# ai_LED_pendant.net
KiCad netlist of a schematic drawn in EAGLE
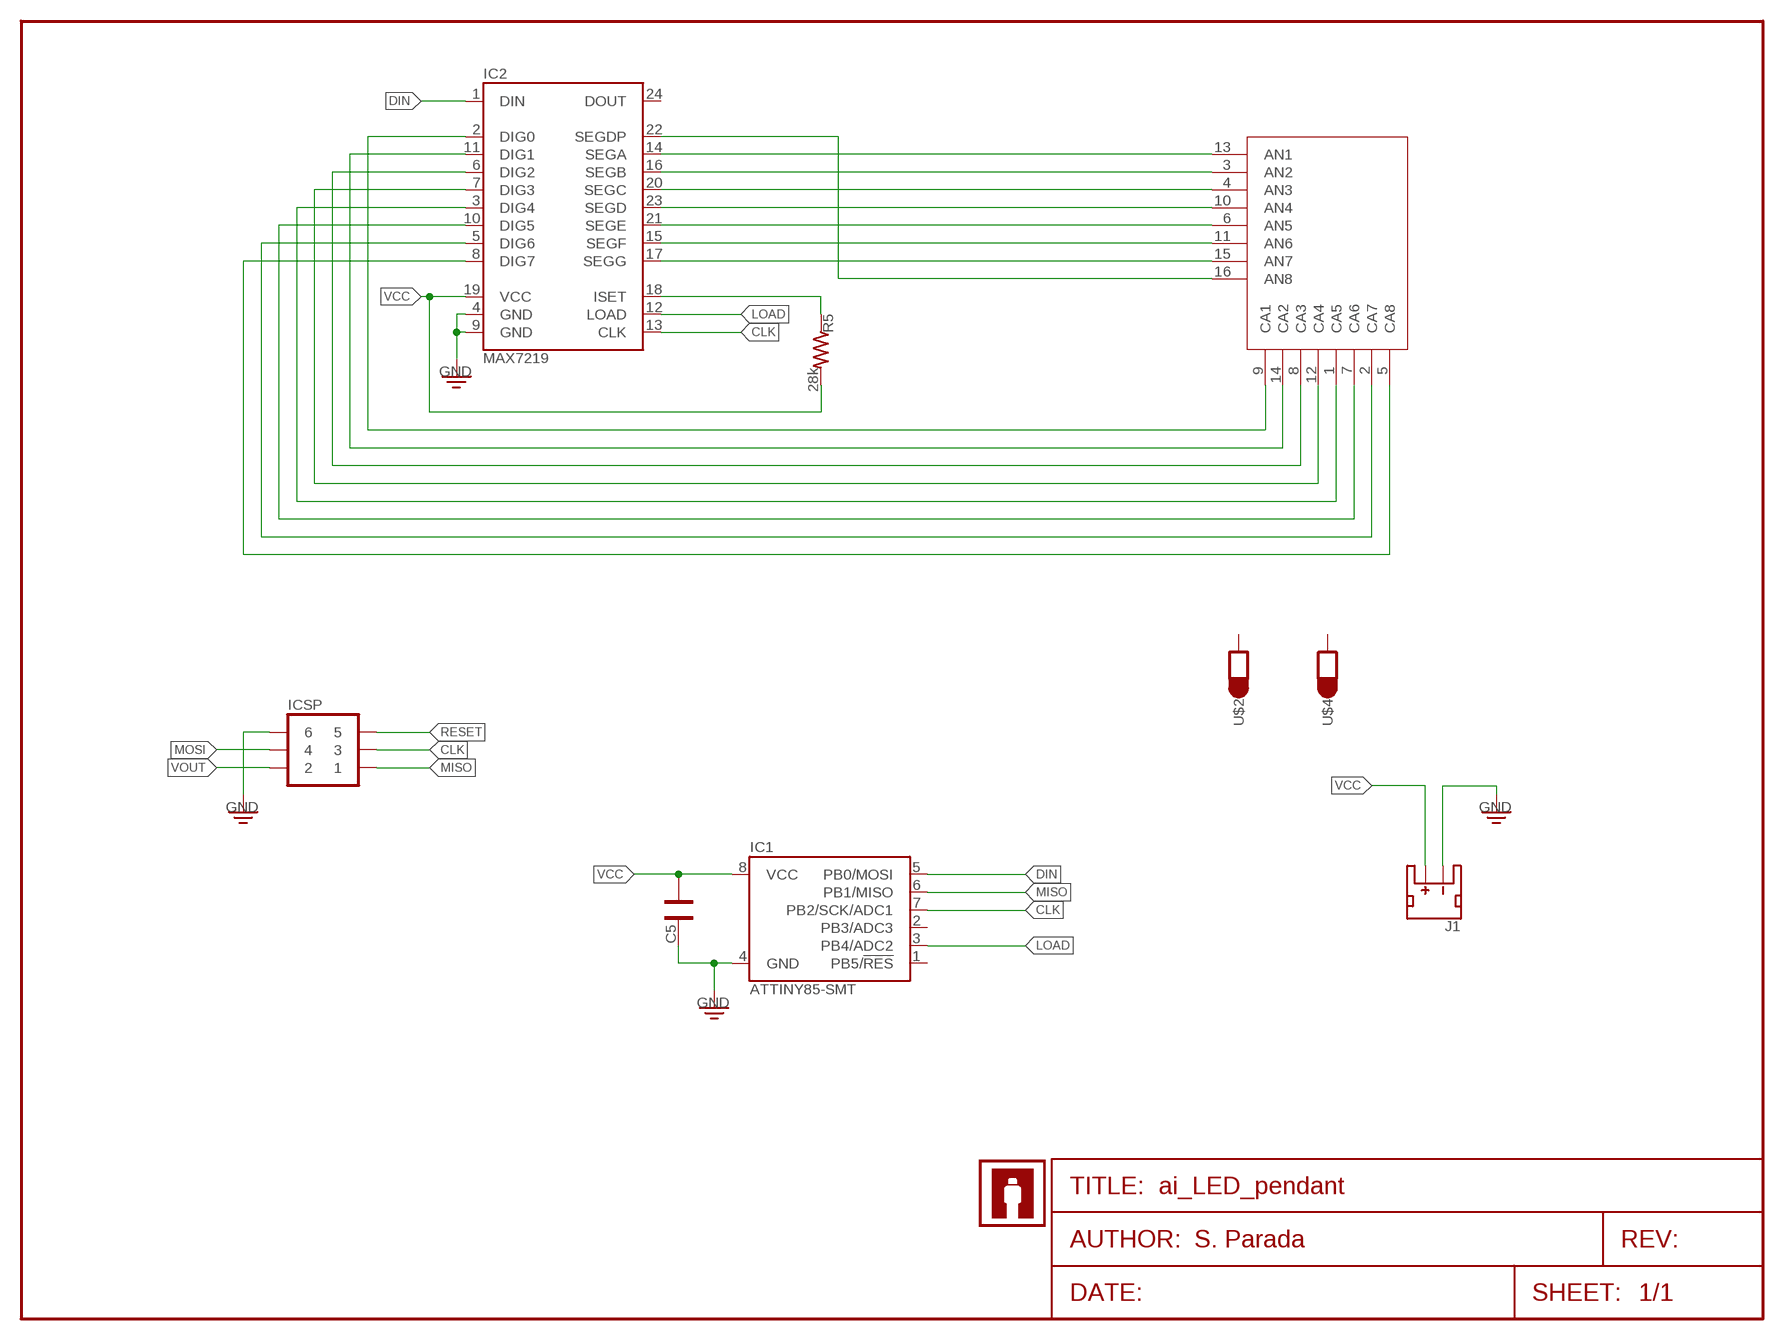
[diagram p0: schematic, sheet 1]

(export (version "E")
  (design (tool "Eeschema 10.0.6"))
  (components
    (comp (ref "C5")
      (value "CAP0402")
      (footprint "eagle-import:CAP-0402")
      (libsource (lib "eagle-import") (part "CAP0402"))
    )
    (comp (ref "IC1")
      (value "ATTINY85-SMT")
      (footprint "eagle-import:SO08-EIAJ")
      (libsource (lib "eagle-import") (part "ATTINY85-SMT"))
    )
    (comp (ref "IC2")
      (value "MAX7219-SMD")
      (footprint "eagle-import:SOIC24")
      (libsource (lib "eagle-import") (part "MAX7219-SMD"))
    )
    (comp (ref "ICSP")
      (value "2X032X03-ICSP-SMALL")
      (footprint "eagle-import:2X03-ICSP-SMALL")
      (libsource (lib "eagle-import") (part "2X032X03-ICSP-SMALL"))
    )
    (comp (ref "J1")
      (value "JST-2P-MALE")
      (footprint "eagle-import:JST-2P-SMD")
      (libsource (lib "eagle-import") (part "JST-2P-MALE"))
    )
    (comp (ref "MATRIX")
      (value "MATRIX-8X8-SINGLE")
      (footprint "eagle-import:LEDM88SMR")
      (libsource (lib "eagle-import") (part "MATRIX-8X8-SINGLE"))
    )
    (comp (ref "R5")
      (value "28k")
      (footprint "eagle-import:RES-0402")
      (libsource (lib "eagle-import") (part "RES0402"))
    )
    (comp (ref "U$1")
      (value "AI-LOGOXS")
      (footprint "eagle-import:AI-LOGO-XS")
      (libsource (lib "eagle-import") (part "AI-LOGOXS"))
    )
    (comp (ref "U$2")
      (value "1X01-PETAL")
      (footprint "eagle-import:1X01-PETAL")
      (libsource (lib "eagle-import") (part "1X01-PETAL"))
    )
    (comp (ref "U$4")
      (value "1X01-PETAL")
      (footprint "eagle-import:1X01-PETAL")
      (libsource (lib "eagle-import") (part "1X01-PETAL"))
    )
  )
  (nets
    (net (code "1") (name "CLK") (class "Default")
      (node (ref "IC1") (pin "7") (pinfunction "PB2/SCK/ADC1_7") (pintype "bidirectional"))
      (node (ref "IC2") (pin "13") (pinfunction "CLK_13") (pintype "bidirectional"))
      (node (ref "ICSP") (pin "3") (pinfunction "3_3") (pintype "bidirectional"))
    )
    (net (code "2") (name "DIN") (class "Default")
      (node (ref "IC1") (pin "5") (pinfunction "PB0/MOSI_5") (pintype "bidirectional"))
      (node (ref "IC2") (pin "1") (pinfunction "DIN_1") (pintype "bidirectional"))
    )
    (net (code "3") (name "GND") (class "Default")
      (node (ref "C5") (pin "2") (pinfunction "2_2") (pintype "passive"))
      (node (ref "IC1") (pin "4") (pinfunction "GND_4") (pintype "bidirectional"))
      (node (ref "IC2") (pin "4") (pinfunction "GND_4") (pintype "bidirectional"))
      (node (ref "IC2") (pin "9") (pinfunction "GND_9") (pintype "bidirectional"))
      (node (ref "ICSP") (pin "6") (pinfunction "6_6") (pintype "bidirectional"))
      (node (ref "J1") (pin "2") (pinfunction "-_2") (pintype "power_in"))
    )
    (net (code "4") (name "LOAD") (class "Default")
      (node (ref "IC1") (pin "3") (pinfunction "PB4/ADC2_3") (pintype "bidirectional"))
      (node (ref "IC2") (pin "12") (pinfunction "LOAD_12") (pintype "bidirectional"))
    )
    (net (code "5") (name "MISO") (class "Default")
      (node (ref "IC1") (pin "6") (pinfunction "PB1/MISO_6") (pintype "bidirectional"))
      (node (ref "ICSP") (pin "1") (pinfunction "1_1") (pintype "bidirectional"))
    )
    (net (code "6") (name "MOSI") (class "Default")
      (node (ref "ICSP") (pin "4") (pinfunction "4_4") (pintype "bidirectional"))
    )
    (net (code "7") (name "Net-(IC2-DIG0)") (class "Default")
      (node (ref "IC2") (pin "2") (pinfunction "DIG0_2") (pintype "bidirectional"))
      (node (ref "MATRIX") (pin "9") (pinfunction "CA1_9") (pintype "bidirectional"))
    )
    (net (code "8") (name "Net-(IC2-DIG1)") (class "Default")
      (node (ref "IC2") (pin "11") (pinfunction "DIG1_11") (pintype "bidirectional"))
      (node (ref "MATRIX") (pin "14") (pinfunction "CA2_14") (pintype "bidirectional"))
    )
    (net (code "9") (name "Net-(IC2-DIG2)") (class "Default")
      (node (ref "IC2") (pin "6") (pinfunction "DIG2_6") (pintype "bidirectional"))
      (node (ref "MATRIX") (pin "8") (pinfunction "CA3_8") (pintype "bidirectional"))
    )
    (net (code "10") (name "Net-(IC2-DIG3)") (class "Default")
      (node (ref "IC2") (pin "7") (pinfunction "DIG3_7") (pintype "bidirectional"))
      (node (ref "MATRIX") (pin "12") (pinfunction "CA4_12") (pintype "bidirectional"))
    )
    (net (code "11") (name "Net-(IC2-DIG4)") (class "Default")
      (node (ref "IC2") (pin "3") (pinfunction "DIG4_3") (pintype "bidirectional"))
      (node (ref "MATRIX") (pin "1") (pinfunction "CA5_1") (pintype "bidirectional"))
    )
    (net (code "12") (name "Net-(IC2-DIG5)") (class "Default")
      (node (ref "IC2") (pin "10") (pinfunction "DIG5_10") (pintype "bidirectional"))
      (node (ref "MATRIX") (pin "7") (pinfunction "CA6_7") (pintype "bidirectional"))
    )
    (net (code "13") (name "Net-(IC2-DIG6)") (class "Default")
      (node (ref "IC2") (pin "5") (pinfunction "DIG6_5") (pintype "bidirectional"))
      (node (ref "MATRIX") (pin "2") (pinfunction "CA7_2") (pintype "bidirectional"))
    )
    (net (code "14") (name "Net-(IC2-DIG7)") (class "Default")
      (node (ref "IC2") (pin "8") (pinfunction "DIG7_8") (pintype "bidirectional"))
      (node (ref "MATRIX") (pin "5") (pinfunction "CA8_5") (pintype "bidirectional"))
    )
    (net (code "15") (name "Net-(IC2-ISET)") (class "Default")
      (node (ref "IC2") (pin "18") (pinfunction "ISET_18") (pintype "bidirectional"))
      (node (ref "R5") (pin "1") (pinfunction "1_1") (pintype "passive"))
    )
    (net (code "16") (name "Net-(IC2-SEGA)") (class "Default")
      (node (ref "IC2") (pin "14") (pinfunction "SEGA_14") (pintype "bidirectional"))
      (node (ref "MATRIX") (pin "13") (pinfunction "AN1_13") (pintype "input"))
    )
    (net (code "17") (name "Net-(IC2-SEGB)") (class "Default")
      (node (ref "IC2") (pin "16") (pinfunction "SEGB_16") (pintype "bidirectional"))
      (node (ref "MATRIX") (pin "3") (pinfunction "AN2_3") (pintype "bidirectional"))
    )
    (net (code "18") (name "Net-(IC2-SEGC)") (class "Default")
      (node (ref "IC2") (pin "20") (pinfunction "SEGC_20") (pintype "bidirectional"))
      (node (ref "MATRIX") (pin "4") (pinfunction "AN3_4") (pintype "bidirectional"))
    )
    (net (code "19") (name "Net-(IC2-SEGD)") (class "Default")
      (node (ref "IC2") (pin "23") (pinfunction "SEGD_23") (pintype "bidirectional"))
      (node (ref "MATRIX") (pin "10") (pinfunction "AN4_10") (pintype "bidirectional"))
    )
    (net (code "20") (name "Net-(IC2-SEGDP)") (class "Default")
      (node (ref "IC2") (pin "22") (pinfunction "SEGDP_22") (pintype "bidirectional"))
      (node (ref "MATRIX") (pin "16") (pinfunction "AN8_16") (pintype "bidirectional"))
    )
    (net (code "21") (name "Net-(IC2-SEGE)") (class "Default")
      (node (ref "IC2") (pin "21") (pinfunction "SEGE_21") (pintype "bidirectional"))
      (node (ref "MATRIX") (pin "6") (pinfunction "AN5_6") (pintype "bidirectional"))
    )
    (net (code "22") (name "Net-(IC2-SEGF)") (class "Default")
      (node (ref "IC2") (pin "15") (pinfunction "SEGF_15") (pintype "bidirectional"))
      (node (ref "MATRIX") (pin "11") (pinfunction "AN6_11") (pintype "bidirectional"))
    )
    (net (code "23") (name "Net-(IC2-SEGG)") (class "Default")
      (node (ref "IC2") (pin "17") (pinfunction "SEGG_17") (pintype "bidirectional"))
      (node (ref "MATRIX") (pin "15") (pinfunction "AN7_15") (pintype "bidirectional"))
    )
    (net (code "24") (name "RESET") (class "Default")
      (node (ref "ICSP") (pin "5") (pinfunction "5_5") (pintype "bidirectional"))
    )
    (net (code "25") (name "VCC") (class "Default")
      (node (ref "C5") (pin "1") (pinfunction "1_1") (pintype "passive"))
      (node (ref "IC1") (pin "8") (pinfunction "VCC_8") (pintype "bidirectional"))
      (node (ref "IC2") (pin "19") (pinfunction "VCC_19") (pintype "bidirectional"))
      (node (ref "J1") (pin "1") (pinfunction "+_1") (pintype "power_in"))
      (node (ref "R5") (pin "2") (pinfunction "2_2") (pintype "passive"))
    )
    (net (code "26") (name "VOUT") (class "Default")
      (node (ref "ICSP") (pin "2") (pinfunction "2_2") (pintype "bidirectional"))
    )
    (net (code "27") (name "unconnected-(IC1-PB3{slash}ADC3-Pad2)") (class "Default")
      (node (ref "IC1") (pin "2") (pinfunction "PB3/ADC3_2") (pintype "bidirectional"))
    )
    (net (code "28") (name "unconnected-(IC1-PB5{slash}~{RES}-Pad1)") (class "Default")
      (node (ref "IC1") (pin "1") (pinfunction "PB5/~{RES}_1") (pintype "bidirectional"))
    )
    (net (code "29") (name "unconnected-(IC2-DOUT-Pad24)") (class "Default")
      (node (ref "IC2") (pin "24") (pinfunction "DOUT_24") (pintype "bidirectional"))
    )
    (net (code "30") (name "unconnected-(U$2-Pad1)") (class "Default")
      (node (ref "U$2") (pin "1") (pinfunction "1_1") (pintype "bidirectional"))
    )
    (net (code "31") (name "unconnected-(U$4-Pad1)") (class "Default")
      (node (ref "U$4") (pin "1") (pinfunction "1_1") (pintype "bidirectional"))
    )
  )
)
